# RTL-SDR.net
KiCad netlist of a schematic drawn in Altium Designer
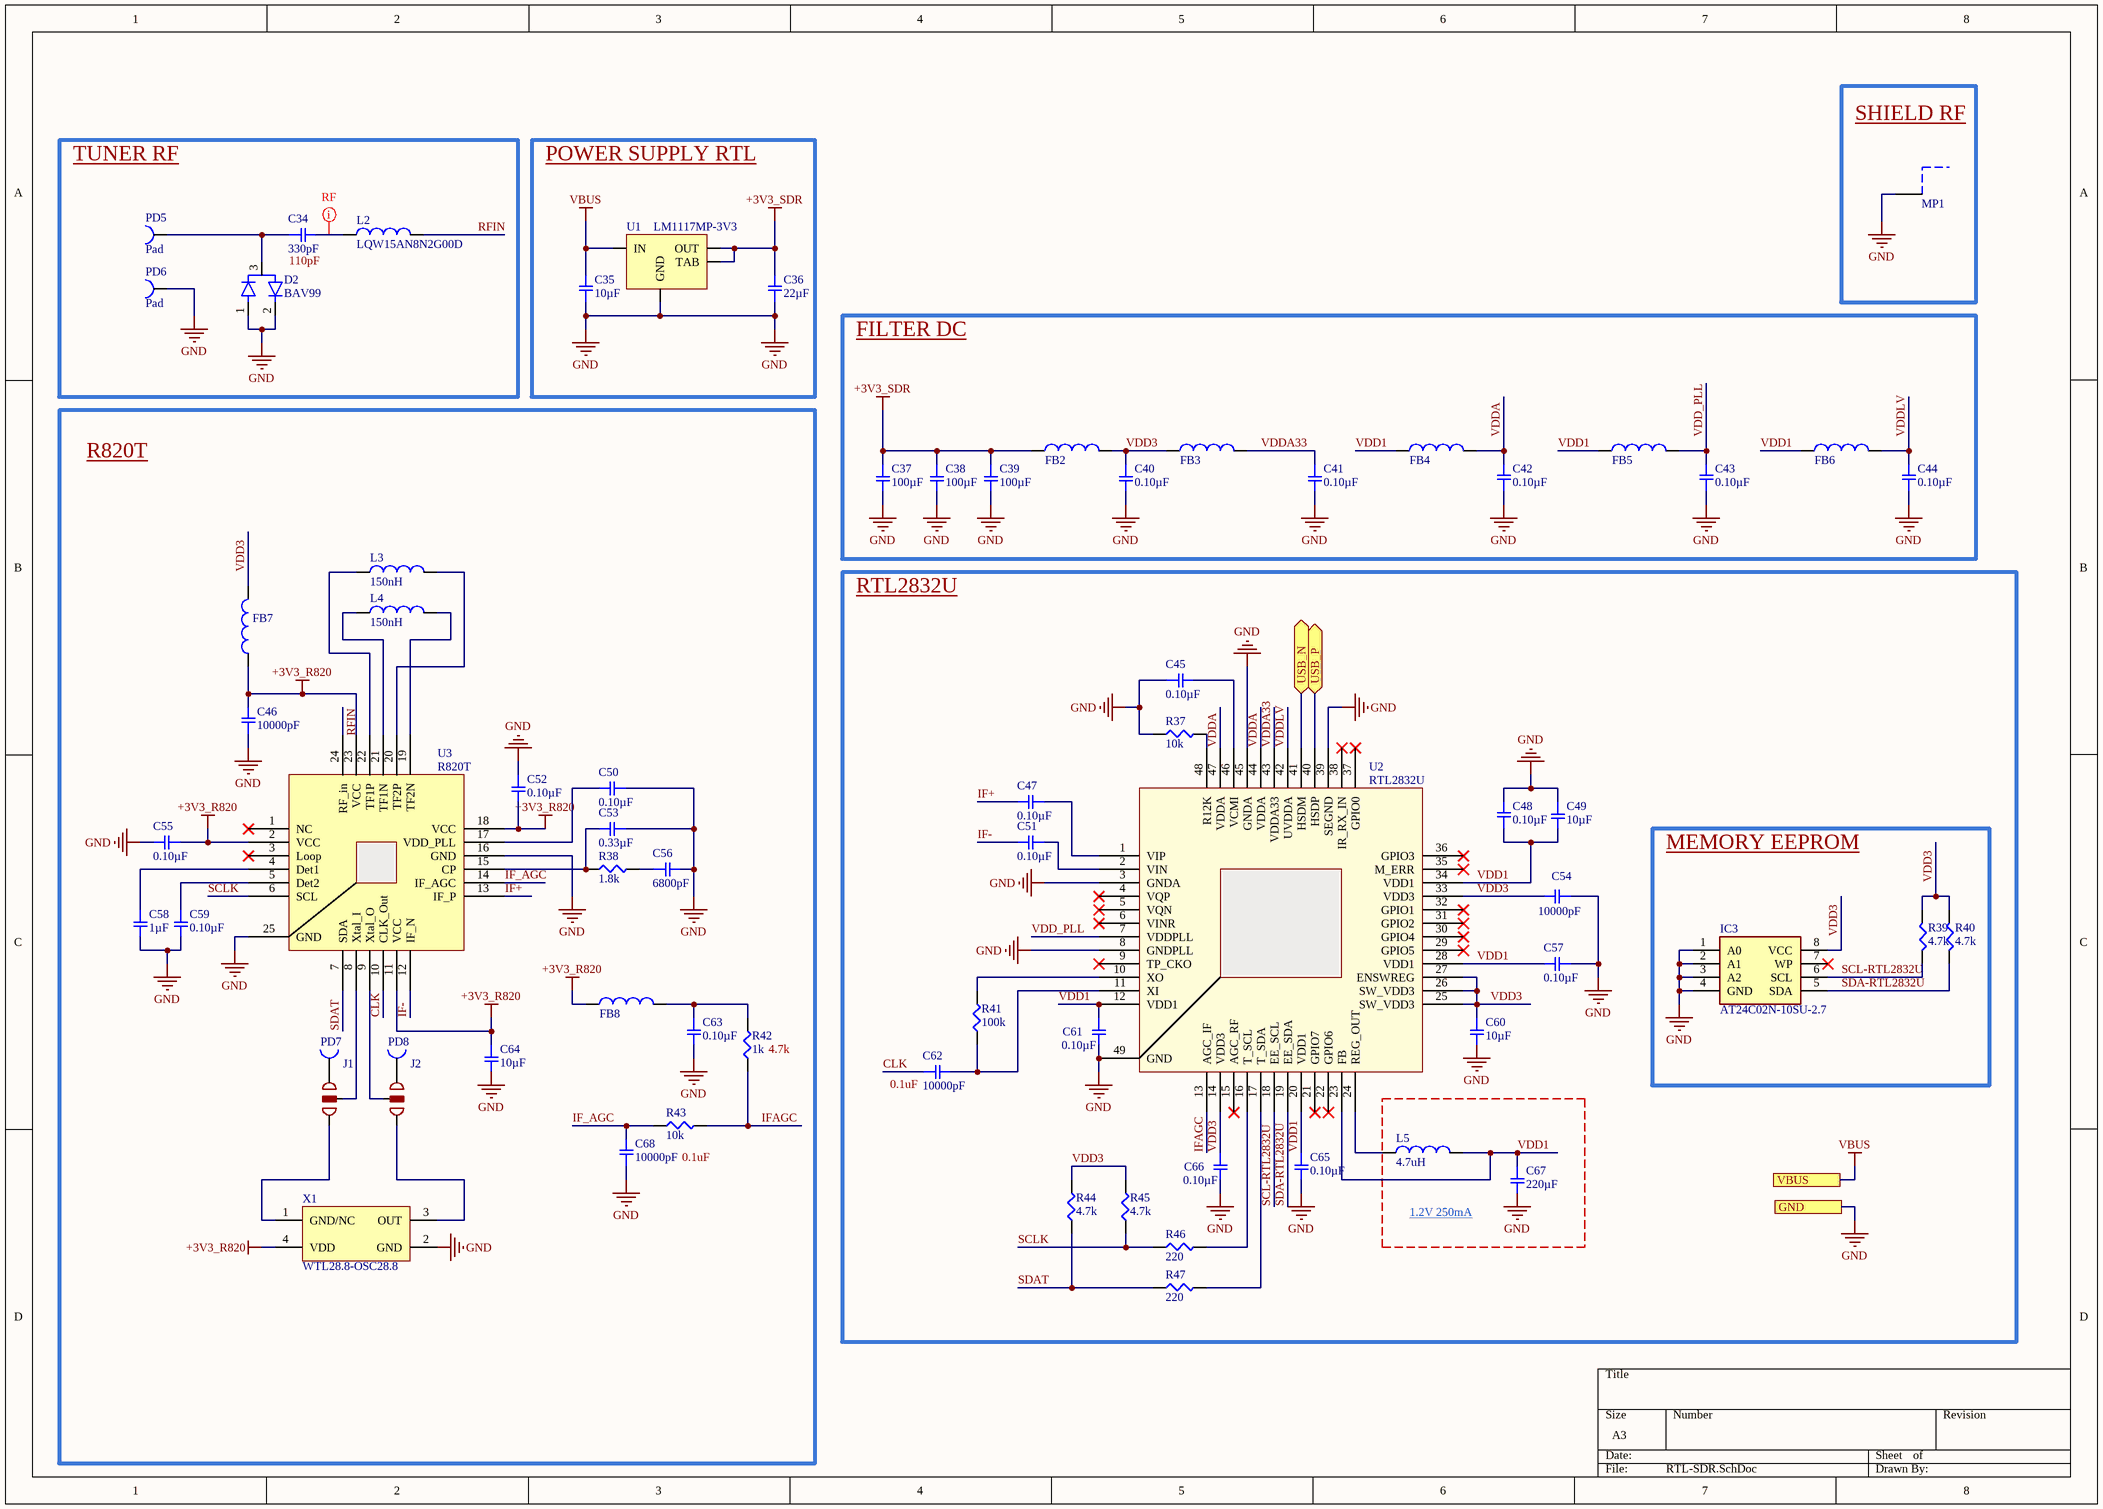
[diagram p0: RTL-SDR.SchDoc]

(export (version "E")
  (design (tool "Eeschema 10.0.6"))
  (components
    (comp (ref "C34")
      (value "330pF")
      (footprint "SMD-0402C")
      (description "CAP CER 330PF 25V NP0 0402")
      (fields
        (field (name "PART NUMBER") "GRM1555C1E331JA01D")
        (field (name "DIGI-KEY PART NUMBER") "490-8176-1-ND")
      )
      (libsource (lib "cap_murata") (part "CAPACITOR"))
    )
    (comp (ref "C35")
      (value "10µF")
      (footprint "SMD-0805C")
      (description "CAP CER 10UF 16V X6S 0805")
      (fields
        (field (name "PART NUMBER") "GRT21BC81C106KE01L")
        (field (name "DIGI-KEY PART NUMBER") "490-12343-1-ND")
      )
      (libsource (lib "cap_murata") (part "CAPACITOR"))
    )
    (comp (ref "C36")
      (value "22µF")
      (footprint "SMD-0805C")
      (description "CAP CER 22UF 16V X5R 0805")
      (fields
        (field (name "PART NUMBER") "GRT21BR61C226ME13L")
        (field (name "DIGI-KEY PART NUMBER") "490-12383-1-ND")
      )
      (libsource (lib "cap_murata") (part "CAPACITOR"))
    )
    (comp (ref "C37")
      (value "100µF")
      (footprint "SMD-1210C")
      (description "CAP CER 100UF 6.3V X7S 1210")
      (fields
        (field (name "PART NUMBER") "GRM32EC70J107ME15L")
        (field (name "DIGI-KEY PART NUMBER") "490-10530-1-ND")
      )
      (libsource (lib "cap_murata") (part "CAPACITOR"))
    )
    (comp (ref "C38")
      (value "100µF")
      (footprint "SMD-1210C")
      (description "CAP CER 100UF 6.3V X7S 1210")
      (fields
        (field (name "PART NUMBER") "GRM32EC70J107ME15L")
        (field (name "DIGI-KEY PART NUMBER") "490-10530-1-ND")
      )
      (libsource (lib "cap_murata") (part "CAPACITOR"))
    )
    (comp (ref "C39")
      (value "100µF")
      (footprint "SMD-1210C")
      (description "CAP CER 100UF 6.3V X7S 1210")
      (fields
        (field (name "PART NUMBER") "GRM32EC70J107ME15L")
        (field (name "DIGI-KEY PART NUMBER") "490-10530-1-ND")
      )
      (libsource (lib "cap_murata") (part "CAPACITOR"))
    )
    (comp (ref "C40")
      (value "0.10µF")
      (footprint "SMD-0402C")
      (description "CAP CER 0.1UF 16V X7R 0402")
      (fields
        (field (name "PART NUMBER") "GCM155R71C104KA55J")
        (field (name "DIGI-KEY PART NUMBER") "490-7998-1-ND")
      )
      (libsource (lib "cap_murata") (part "CAPACITOR"))
    )
    (comp (ref "C41")
      (value "0.10µF")
      (footprint "SMD-0402C")
      (description "CAP CER 0.1UF 16V X7R 0402")
      (fields
        (field (name "PART NUMBER") "GCM155R71C104KA55J")
        (field (name "DIGI-KEY PART NUMBER") "490-7998-1-ND")
      )
      (libsource (lib "cap_murata") (part "CAPACITOR"))
    )
    (comp (ref "C42")
      (value "0.10µF")
      (footprint "SMD-0402C")
      (description "CAP CER 0.1UF 16V X7R 0402")
      (fields
        (field (name "PART NUMBER") "GCM155R71C104KA55J")
        (field (name "DIGI-KEY PART NUMBER") "490-7998-1-ND")
      )
      (libsource (lib "cap_murata") (part "CAPACITOR"))
    )
    (comp (ref "C43")
      (value "0.10µF")
      (footprint "SMD-0402C")
      (description "CAP CER 0.1UF 16V X7R 0402")
      (fields
        (field (name "PART NUMBER") "GCM155R71C104KA55J")
        (field (name "DIGI-KEY PART NUMBER") "490-7998-1-ND")
      )
      (libsource (lib "cap_murata") (part "CAPACITOR"))
    )
    (comp (ref "C44")
      (value "0.10µF")
      (footprint "SMD-0402C")
      (description "CAP CER 0.1UF 16V X7R 0402")
      (fields
        (field (name "PART NUMBER") "GCM155R71C104KA55J")
        (field (name "DIGI-KEY PART NUMBER") "490-7998-1-ND")
      )
      (libsource (lib "cap_murata") (part "CAPACITOR"))
    )
    (comp (ref "C45")
      (value "0.10µF")
      (footprint "SMD-0402C")
      (description "CAP CER 0.1UF 16V X7R 0402")
      (fields
        (field (name "PART NUMBER") "GCM155R71C104KA55J")
        (field (name "DIGI-KEY PART NUMBER") "490-7998-1-ND")
      )
      (libsource (lib "cap_murata") (part "CAPACITOR"))
    )
    (comp (ref "C46")
      (value "10000pF")
      (footprint "SMD-0402C")
      (description "CAP CER 10000PF 16V X7R 0402")
      (fields
        (field (name "PART NUMBER") "GRM155R71C103KA01J")
        (field (name "DIGI-KEY PART NUMBER") "490-6326-1-ND")
      )
      (libsource (lib "cap_murata") (part "CAPACITOR"))
    )
    (comp (ref "C47")
      (value "0.10µF")
      (footprint "SMD-0402C")
      (description "CAP CER 0.1UF 16V X7R 0402")
      (fields
        (field (name "PART NUMBER") "GCM155R71C104KA55J")
        (field (name "DIGI-KEY PART NUMBER") "490-7998-1-ND")
      )
      (libsource (lib "cap_murata") (part "CAPACITOR"))
    )
    (comp (ref "C48")
      (value "0.10µF")
      (footprint "SMD-0402C")
      (description "CAP CER 0.1UF 16V X7R 0402")
      (fields
        (field (name "PART NUMBER") "GCM155R71C104KA55J")
        (field (name "DIGI-KEY PART NUMBER") "490-7998-1-ND")
      )
      (libsource (lib "cap_murata") (part "CAPACITOR"))
    )
    (comp (ref "C49")
      (value "10µF")
      (footprint "SMD-0603C")
      (description "CAP CER 10UF 16V X6S 0603")
      (fields
        (field (name "PART NUMBER") "GRT188C81C106ME13D")
        (field (name "DIGI-KEY PART NUMBER") "490-12286-1-ND")
      )
      (libsource (lib "cap_murata") (part "CAPACITOR"))
    )
    (comp (ref "C50")
      (value "0.10µF")
      (footprint "SMD-0402C")
      (description "CAP CER 0.1UF 16V X7R 0402")
      (fields
        (field (name "PART NUMBER") "GCM155R71C104KA55J")
        (field (name "DIGI-KEY PART NUMBER") "490-7998-1-ND")
      )
      (libsource (lib "cap_murata") (part "CAPACITOR"))
    )
    (comp (ref "C51")
      (value "0.10µF")
      (footprint "SMD-0402C")
      (description "CAP CER 0.1UF 16V X7R 0402")
      (fields
        (field (name "PART NUMBER") "GCM155R71C104KA55J")
        (field (name "DIGI-KEY PART NUMBER") "490-7998-1-ND")
      )
      (libsource (lib "cap_murata") (part "CAPACITOR"))
    )
    (comp (ref "C52")
      (value "0.10µF")
      (footprint "SMD-0402C")
      (description "CAP CER 0.1UF 16V X7R 0402")
      (fields
        (field (name "PART NUMBER") "GCM155R71C104KA55J")
        (field (name "DIGI-KEY PART NUMBER") "490-7998-1-ND")
      )
      (libsource (lib "cap_murata") (part "CAPACITOR"))
    )
    (comp (ref "C53")
      (value "0.33µF")
      (footprint "SMD-0402C")
      (description "CAP CER 0.33UF 10V X5R 0402")
      (fields
        (field (name "PART NUMBER") "GRM155R61A334KE15D")
        (field (name "DIGI-KEY PART NUMBER") "490-3263-1-ND")
      )
      (libsource (lib "cap_murata") (part "CAPACITOR"))
    )
    (comp (ref "C54")
      (value "10000pF")
      (footprint "SMD-0402C")
      (description "CAP CER 10000PF 16V X7R 0402")
      (fields
        (field (name "PART NUMBER") "GRM155R71C103KA01J")
        (field (name "DIGI-KEY PART NUMBER") "490-6326-1-ND")
      )
      (libsource (lib "cap_murata") (part "CAPACITOR"))
    )
    (comp (ref "C55")
      (value "0.10µF")
      (footprint "SMD-0402C")
      (description "CAP CER 0.1UF 16V X7R 0402")
      (fields
        (field (name "PART NUMBER") "GCM155R71C104KA55J")
        (field (name "DIGI-KEY PART NUMBER") "490-7998-1-ND")
      )
      (libsource (lib "cap_murata") (part "CAPACITOR"))
    )
    (comp (ref "C56")
      (value "6800pF")
      (footprint "SMD-0402C")
      (description "CAP CER 6800PF 25V X7R 0402")
      (fields
        (field (name "PART NUMBER") "GRM155R71E682KA01D")
        (field (name "DIGI-KEY PART NUMBER") "490-1310-1-ND")
      )
      (libsource (lib "cap_murata") (part "CAPACITOR"))
    )
    (comp (ref "C57")
      (value "0.10µF")
      (footprint "SMD-0402C")
      (description "CAP CER 0.1UF 16V X7R 0402")
      (fields
        (field (name "PART NUMBER") "GCM155R71C104KA55J")
        (field (name "DIGI-KEY PART NUMBER") "490-7998-1-ND")
      )
      (libsource (lib "cap_murata") (part "CAPACITOR"))
    )
    (comp (ref "C58")
      (value "1µF")
      (footprint "SMD-0402C")
      (description "CAP CER 1UF 25V X5R 0402")
      (fields
        (field (name "PART NUMBER") "GRM155R61E105MA12D")
        (field (name "DIGI-KEY PART NUMBER") "490-10018-1-ND")
      )
      (libsource (lib "cap_murata") (part "CAPACITOR"))
    )
    (comp (ref "C59")
      (value "0.10µF")
      (footprint "SMD-0402C")
      (description "CAP CER 0.1UF 16V X7R 0402")
      (fields
        (field (name "PART NUMBER") "GCM155R71C104KA55J")
        (field (name "DIGI-KEY PART NUMBER") "490-7998-1-ND")
      )
      (libsource (lib "cap_murata") (part "CAPACITOR"))
    )
    (comp (ref "C60")
      (value "10µF")
      (footprint "SMD-0603C")
      (description "CAP CER 10UF 16V X6S 0603")
      (fields
        (field (name "PART NUMBER") "GRT188C81C106ME13D")
        (field (name "DIGI-KEY PART NUMBER") "490-12286-1-ND")
      )
      (libsource (lib "cap_murata") (part "CAPACITOR"))
    )
    (comp (ref "C61")
      (value "0.10µF")
      (footprint "SMD-0402C")
      (description "CAP CER 0.1UF 16V X7R 0402")
      (fields
        (field (name "PART NUMBER") "GCM155R71C104KA55J")
        (field (name "DIGI-KEY PART NUMBER") "490-7998-1-ND")
      )
      (libsource (lib "cap_murata") (part "CAPACITOR"))
    )
    (comp (ref "C62")
      (value "10000pF")
      (footprint "SMD-0402C")
      (description "CAP CER 10000PF 16V X7R 0402")
      (fields
        (field (name "PART NUMBER") "GRM155R71C103KA01D")
        (field (name "DIGI-KEY PART NUMBER") "490-1313-1-ND")
      )
      (libsource (lib "cap_murata") (part "CAPACITOR"))
    )
    (comp (ref "C63")
      (value "0.10µF")
      (footprint "SMD-0402C")
      (description "CAP CER 0.1UF 16V X7R 0402")
      (fields
        (field (name "PART NUMBER") "GCM155R71C104KA55J")
        (field (name "DIGI-KEY PART NUMBER") "490-7998-1-ND")
      )
      (libsource (lib "cap_murata") (part "CAPACITOR"))
    )
    (comp (ref "C64")
      (value "10µF")
      (footprint "SMD-0805C")
      (description "CAP CER 10UF 16V X6S 0805")
      (fields
        (field (name "PART NUMBER") "GRT21BC81C106KE01L")
        (field (name "DIGI-KEY PART NUMBER") "490-12343-1-ND")
      )
      (libsource (lib "cap_murata") (part "CAPACITOR"))
    )
    (comp (ref "C65")
      (value "0.10µF")
      (footprint "SMD-0402C")
      (description "CAP CER 0.1UF 16V X7R 0402")
      (fields
        (field (name "PART NUMBER") "GCM155R71C104KA55J")
        (field (name "DIGI-KEY PART NUMBER") "490-7998-1-ND")
      )
      (libsource (lib "cap_murata") (part "CAPACITOR"))
    )
    (comp (ref "C66")
      (value "0.10µF")
      (footprint "SMD-0402C")
      (description "CAP CER 0.1UF 16V X7R 0402")
      (fields
        (field (name "PART NUMBER") "GCM155R71C104KA55J")
        (field (name "DIGI-KEY PART NUMBER") "490-7998-1-ND")
      )
      (libsource (lib "cap_murata") (part "CAPACITOR"))
    )
    (comp (ref "C67")
      (value "220µF")
      (footprint "SMD-1210C")
      (description "CAP CER 220UF 4V X6S 1210")
      (fields
        (field (name "PART NUMBER") "GRM32EC80G227ME05L")
        (field (name "DIGI-KEY PART NUMBER") "490-13973-1-ND")
      )
      (libsource (lib "cap_murata") (part "CAPACITOR"))
    )
    (comp (ref "C68")
      (value "10000pF")
      (footprint "SMD-0402C")
      (description "CAP CER 10000PF 16V X7R 0402")
      (fields
        (field (name "PART NUMBER") "GRM155R71C103KA01J")
        (field (name "DIGI-KEY PART NUMBER") "490-6326-1-ND")
      )
      (libsource (lib "cap_murata") (part "CAPACITOR"))
    )
    (comp (ref "D2")
      (value "BAV99")
      (footprint "DIO_BAV99")
      (fields (field (name "MF") "ON Semiconductor"))
      (libsource (lib "DSD_Aerobits_RPI4_OLED") (part "BAV99"))
    )
    (comp (ref "FB2")
      (value "10Ohm")
      (footprint "WE-CBA_0402_L1W0.5H0.5_HC")
      (description "WE-CBA SMT EMI Suppression Ferrite Bead, size 0402, 10Ohm, 1.5A")
      (fields
        (field (name "MANUFACTURER PART NUMBER") "782423100")
        (field (name "MANUFACTURER") "Wurth Elektronik")
      )
      (libsource (lib "Altium_WE-CBA (rev22d)") (part "782423100"))
    )
    (comp (ref "FB3")
      (value "10Ohm")
      (footprint "WE-CBA_0402_L1W0.5H0.5_HC")
      (description "WE-CBA SMT EMI Suppression Ferrite Bead, size 0402, 10Ohm, 1.5A")
      (fields
        (field (name "MANUFACTURER PART NUMBER") "782423100")
        (field (name "MANUFACTURER") "Wurth Elektronik")
      )
      (libsource (lib "Altium_WE-CBA (rev22d)") (part "782423100"))
    )
    (comp (ref "FB4")
      (value "10Ohm")
      (footprint "WE-CBA_0402_L1W0.5H0.5_HC")
      (description "WE-CBA SMT EMI Suppression Ferrite Bead, size 0402, 10Ohm, 1.5A")
      (fields
        (field (name "MANUFACTURER PART NUMBER") "782423100")
        (field (name "MANUFACTURER") "Wurth Elektronik")
      )
      (libsource (lib "Altium_WE-CBA (rev22d)") (part "782423100"))
    )
    (comp (ref "FB5")
      (value "10Ohm")
      (footprint "WE-CBA_0402_L1W0.5H0.5_HC")
      (description "WE-CBA SMT EMI Suppression Ferrite Bead, size 0402, 10Ohm, 1.5A")
      (fields
        (field (name "MANUFACTURER PART NUMBER") "782423100")
        (field (name "MANUFACTURER") "Wurth Elektronik")
      )
      (libsource (lib "Altium_WE-CBA (rev22d)") (part "782423100"))
    )
    (comp (ref "FB6")
      (value "10Ohm")
      (footprint "WE-CBA_0402_L1W0.5H0.5_HC")
      (description "WE-CBA SMT EMI Suppression Ferrite Bead, size 0402, 10Ohm, 1.5A")
      (fields
        (field (name "MANUFACTURER PART NUMBER") "782423100")
        (field (name "MANUFACTURER") "Wurth Elektronik")
      )
      (libsource (lib "Altium_WE-CBA (rev22d)") (part "782423100"))
    )
    (comp (ref "FB7")
      (value "10Ohm")
      (footprint "WE-CBA_0402_L1W0.5H0.5_HC")
      (description "WE-CBA SMT EMI Suppression Ferrite Bead, size 0402, 10Ohm, 1.5A")
      (fields
        (field (name "MANUFACTURER PART NUMBER") "782423100")
        (field (name "MANUFACTURER") "Wurth Elektronik")
      )
      (libsource (lib "Altium_WE-CBA (rev22d)") (part "782423100"))
    )
    (comp (ref "FB8")
      (value "10Ohm")
      (footprint "WE-CBA_0402_L1W0.5H0.5_HC")
      (description "WE-CBA SMT EMI Suppression Ferrite Bead, size 0402, 10Ohm, 1.5A")
      (fields
        (field (name "MANUFACTURER PART NUMBER") "782423100")
        (field (name "MANUFACTURER") "Wurth Elektronik")
      )
      (libsource (lib "Altium_WE-CBA (rev22d)") (part "782423100"))
    )
    (comp (ref "IC3")
      (value "AT24C02N-10SU-2.7")
      (footprint "SamacSys:SOIC127P600X175-8N")
      (description "Integrated Circuit")
      (libsource (lib "SamacSys") (part "AT24C02N-10SU-2.7"))
    )
    (comp (ref "J1") (value "jumper") (footprint "jumperTreestate") (libsource (lib "") (part "jumper_1")))
    (comp (ref "J2")
      (value "jumper")
      (footprint "jumperTreestate")
      (libsource (lib "Jumpers") (part "jumper"))
    )
    (comp (ref "L2")
      (value "LQW15AN8N2G00D")
      (footprint "INDC1006X60N")
      (description "LQW15A 0,0082ÂµH 540mA 2% WWT")
      (libsource (lib "DSD_Aerobits_RPI4_OLED") (part "LQW15AN8N2G00D"))
    )
    (comp (ref "L3")
      (value "150nH")
      (footprint "INDC1608X100N")
      (description "CHIP COIL LQW18A")
      (fields (field (name "MP") "LQW18ANR15J00D"))
      (libsource (lib "DSD_Aerobits_RPI4_OLED") (part "LQW18ANR15J00D"))
    )
    (comp (ref "L4")
      (value "150nH")
      (footprint "INDC1608X100N")
      (description "CHIP COIL LQW18A")
      (fields (field (name "MP") "LQW18ANR15J00D"))
      (libsource (lib "DSD_Aerobits_RPI4_OLED") (part "LQW18ANR15J00D"))
    )
    (comp (ref "L5")
      (value "4.7uH")
      (footprint "INDC2518X200N")
      (description "Ind Power Chip Wirewound 4.7uH 20% 7.96MHz Ferrite 1.1A 1007 T/R")
      (fields (field (name "MP") "CB2518T4R7M"))
      (libsource (lib "DSD_Aerobits_RPI4_OLED") (part "CB2518T4R7M"))
    )
    (comp (ref "MP1")
      (value "36903205S")
      (footprint "36903205S")
      (description "WE-SHC Shielding Cabinet, One Piece, Tin Plated, Tape and Reel, 20x20x3mm")
      (fields (field (name "MANUFACTURER") "Wurth Elektronik"))
      (libsource (lib "WE-SHC (rev22a) (1)") (part "36903205S"))
    )
    (comp (ref "PD5") (value "Pad") (footprint "pad") (libsource (lib "Castellated_Pad") (part "Pad")))
    (comp (ref "PD6") (value "Pad") (footprint "pad") (libsource (lib "Castellated_Pad") (part "Pad")))
    (comp (ref "PD7") (value "Pad") (footprint "pad") (libsource (lib "Castellated_Pad") (part "Pad")))
    (comp (ref "PD8") (value "Pad") (footprint "pad") (libsource (lib "Castellated_Pad") (part "Pad")))
    (comp (ref "R37")
      (value "10k")
      (footprint "SMD-0402-RES")
      (description "RES SMD 10K OHM 1% 1/10W 0402")
      (fields
        (field (name "PART NUMBER") "ERJ-2RKF1002X")
        (field (name "DIGI-KEY PART NUMBER") "P10.0KLCT-ND")
      )
      (libsource (lib "res_panasonic_erj_xls") (part "RESISTOR"))
    )
    (comp (ref "R38")
      (value "1.8k")
      (footprint "SMD-0402-RES")
      (description "RES SMD 1.8K OHM 5% 1/10W 0402")
      (fields (field (name "PART NUMBER") "ERJ-2GEJ182X") (field (name "DIGI-KEY PART NUMBER") "P1.8KJCT-ND"))
      (libsource (lib "res_panasonic_erj_xls") (part "RESISTOR"))
    )
    (comp (ref "R39")
      (value "4.7k")
      (footprint "SMD-0402-RES")
      (description "RES SMD 4.7K OHM 1% 1/10W 0402")
      (fields
        (field (name "PART NUMBER") "ERJ-2RKF4701X")
        (field (name "DIGI-KEY PART NUMBER") "P4.70KLCT-ND")
      )
      (libsource (lib "res_panasonic_erj_xls") (part "RESISTOR"))
    )
    (comp (ref "R40")
      (value "4.7k")
      (footprint "SMD-0402-RES")
      (description "RES SMD 4.7K OHM 1% 1/10W 0402")
      (fields
        (field (name "PART NUMBER") "ERJ-2RKF4701X")
        (field (name "DIGI-KEY PART NUMBER") "P4.70KLCT-ND")
      )
      (libsource (lib "res_panasonic_erj_xls") (part "RESISTOR"))
    )
    (comp (ref "R41")
      (value "100k")
      (footprint "SMD-0402-RES")
      (description "RES SMD 100K OHM 1% 1/10W 0402")
      (fields
        (field (name "PART NUMBER") "ERJ-2RKF1003X")
        (field (name "DIGI-KEY PART NUMBER") "P100KLCT-ND")
      )
      (libsource (lib "res_panasonic_erj_xls") (part "RESISTOR"))
    )
    (comp (ref "R42")
      (value "1k")
      (footprint "SMD-0402-RES")
      (description "RES SMD 1K OHM 5% 1/10W 0402")
      (fields (field (name "PART NUMBER") "ERJ-2GEJ102X") (field (name "DIGI-KEY PART NUMBER") "P1.0KJCT-ND"))
      (libsource (lib "res_panasonic_erj_xls") (part "RESISTOR"))
    )
    (comp (ref "R43")
      (value "10k")
      (footprint "SMD-0402-RES")
      (description "RES SMD 10K OHM 1% 1/10W 0402")
      (fields
        (field (name "PART NUMBER") "ERJ-2RKF1002X")
        (field (name "DIGI-KEY PART NUMBER") "P10.0KLCT-ND")
      )
      (libsource (lib "res_panasonic_erj_xls") (part "RESISTOR"))
    )
    (comp (ref "R44")
      (value "4.7k")
      (footprint "SMD-0402-RES")
      (description "RES SMD 4.7K OHM 1% 1/10W 0402")
      (fields
        (field (name "PART NUMBER") "ERJ-2RKF4701X")
        (field (name "DIGI-KEY PART NUMBER") "P4.70KLCT-ND")
      )
      (libsource (lib "res_panasonic_erj_xls") (part "RESISTOR"))
    )
    (comp (ref "R45")
      (value "4.7k")
      (footprint "SMD-0402-RES")
      (description "RES SMD 4.7K OHM 1% 1/10W 0402")
      (fields
        (field (name "PART NUMBER") "ERJ-2RKF4701X")
        (field (name "DIGI-KEY PART NUMBER") "P4.70KLCT-ND")
      )
      (libsource (lib "res_panasonic_erj_xls") (part "RESISTOR"))
    )
    (comp (ref "R46")
      (value "220")
      (footprint "SMD-0402-RES")
      (description "RES SMD 220 OHM 5% 1/5W 0402")
      (fields (field (name "PART NUMBER") "ERJ-PA2J221X") (field (name "DIGI-KEY PART NUMBER") "P17189CT-ND"))
      (libsource (lib "res_panasonic_erj_xls") (part "RESISTOR"))
    )
    (comp (ref "R47")
      (value "220")
      (footprint "SMD-0402-RES")
      (description "RES SMD 220 OHM 5% 1/5W 0402")
      (fields (field (name "PART NUMBER") "ERJ-PA2J221X") (field (name "DIGI-KEY PART NUMBER") "P17189CT-ND"))
      (libsource (lib "res_panasonic_erj_xls") (part "RESISTOR"))
    )
    (comp (ref "U1")
      (value "LM1117MP-3V3")
      (footprint "SOT223")
      (description "800mA Low-Dropout Linear Regulator")
      (fields
        (field (name "PARTNUMBER") "LM1117MP-3.3")
        (field (name "MANUFACTURER") "National Semiconductor")
        (field (name "PUBLISHER") "Altium Limited")
      )
      (libsource (lib "biblioteka_schematic") (part "LM1117MP-3V3"))
    )
    (comp (ref "U2")
      (value "RTL2832U")
      (footprint "QFN40P600X600X84_HS-49N")
      (description "RTL2832U DVB-T COFDM Demodulator + USB 2.0")
      (fields (field (name "MANUFACTURER") "Realtek") (field (name "PUBLISHER") "ftg"))
      (libsource (lib "DSD_Aerobits_RPI4_OLED") (part "RTL2832U"))
    )
    (comp (ref "U3")
      (value "R820T")
      (footprint "QFN50P400X400X85_HS-25N_r820t")
      (libsource (lib "DSD_Aerobits_RPI4_OLED") (part "R820T"))
    )
    (comp (ref "X1")
      (value "WTL28.8-OSC28.8")
      (footprint "WTL28.8-OSC28.8")
      (libsource (lib "DSD_Aerobits_RPI4_OLED") (part "WTL28.8-OSC28.8"))
    )
  )
  (nets
    (net (code "1") (name "+3V3_R820") (class "Default")
      (node (ref "C46") (pin "2") (pinfunction "2_2") (pintype "passive"))
      (node (ref "C52") (pin "2") (pinfunction "2_2") (pintype "passive"))
      (node (ref "C55") (pin "1") (pinfunction "1_1") (pintype "passive"))
      (node (ref "C64") (pin "1") (pinfunction "1_1") (pintype "passive"))
      (node (ref "FB7") (pin "1") (pinfunction "1_1") (pintype "passive"))
      (node (ref "FB8") (pin "1") (pinfunction "1_1") (pintype "passive"))
      (node (ref "U3") (pin "11") (pinfunction "VCC_11") (pintype "passive"))
      (node (ref "U3") (pin "18") (pinfunction "VCC_18") (pintype "passive"))
      (node (ref "U3") (pin "2") (pinfunction "VCC_2") (pintype "passive"))
      (node (ref "U3") (pin "23") (pinfunction "VCC_23") (pintype "passive"))
      (node (ref "X1") (pin "4") (pinfunction "VDD_4") (pintype "passive"))
    )
    (net (code "2") (name "+3V3_SDR") (class "Default")
      (node (ref "C36") (pin "2") (pinfunction "2_2") (pintype "passive"))
      (node (ref "C37") (pin "1") (pinfunction "1_1") (pintype "passive"))
      (node (ref "C38") (pin "1") (pinfunction "1_1") (pintype "passive"))
      (node (ref "C39") (pin "1") (pinfunction "1_1") (pintype "passive"))
      (node (ref "FB2") (pin "1") (pinfunction "1_1") (pintype "passive"))
      (node (ref "U1") (pin "2") (pinfunction "OUT_2") (pintype "power_in"))
      (node (ref "U1") (pin "4") (pinfunction "TAB_4") (pintype "power_in"))
    )
    (net (code "3") (name "/CLK") (class "Default")
      (node (ref "C62") (pin "1") (pinfunction "1_1") (pintype "passive"))
      (node (ref "U3") (pin "10") (pinfunction "CLK_Out_10") (pintype "passive"))
    )
    (net (code "4") (name "/IF+") (class "Default")
      (node (ref "C47") (pin "2") (pinfunction "2_2") (pintype "passive"))
      (node (ref "U3") (pin "13") (pinfunction "IF_P_13") (pintype "passive"))
    )
    (net (code "5") (name "/IF-") (class "Default")
      (node (ref "C51") (pin "2") (pinfunction "2_2") (pintype "passive"))
      (node (ref "U3") (pin "12") (pinfunction "IF_N_12") (pintype "passive"))
    )
    (net (code "6") (name "/IFAGC") (class "Default")
      (node (ref "R42") (pin "1") (pinfunction "1_1") (pintype "passive"))
      (node (ref "R43") (pin "2") (pinfunction "2_2") (pintype "passive"))
      (node (ref "U2") (pin "13") (pinfunction "AGC_IF_13") (pintype "passive"))
    )
    (net (code "7") (name "/IF_AGC") (class "Default")
      (node (ref "C68") (pin "2") (pinfunction "2_2") (pintype "passive"))
      (node (ref "R43") (pin "1") (pinfunction "1_1") (pintype "passive"))
      (node (ref "U3") (pin "14") (pinfunction "IF_AGC_14") (pintype "passive"))
    )
    (net (code "8") (name "/RFIN") (class "Default")
      (node (ref "L2") (pin "2") (pinfunction "2_2") (pintype "passive"))
      (node (ref "U3") (pin "24") (pinfunction "RF_in_24") (pintype "passive"))
    )
    (net (code "9") (name "/SCL-RTL2832U") (class "Default")
      (node (ref "IC3") (pin "6") (pinfunction "SCL_6") (pintype "passive"))
      (node (ref "R39") (pin "1") (pinfunction "1_1") (pintype "passive"))
      (node (ref "U2") (pin "18") (pinfunction "EE_SCL_18") (pintype "passive"))
    )
    (net (code "10") (name "/SCLK") (class "Default")
      (node (ref "R45") (pin "1") (pinfunction "1_1") (pintype "passive"))
      (node (ref "R46") (pin "1") (pinfunction "1_1") (pintype "passive"))
      (node (ref "U3") (pin "6") (pinfunction "SCL_6") (pintype "passive"))
    )
    (net (code "11") (name "/SDA-RTL2832U") (class "Default")
      (node (ref "IC3") (pin "5") (pinfunction "SDA_5") (pintype "passive"))
      (node (ref "R40") (pin "1") (pinfunction "1_1") (pintype "passive"))
      (node (ref "U2") (pin "19") (pinfunction "EE_SDA_19") (pintype "passive"))
    )
    (net (code "12") (name "/SDAT") (class "Default")
      (node (ref "R44") (pin "1") (pinfunction "1_1") (pintype "passive"))
      (node (ref "R47") (pin "1") (pinfunction "1_1") (pintype "passive"))
      (node (ref "U3") (pin "7") (pinfunction "SDA_7") (pintype "passive"))
    )
    (net (code "13") (name "/USB_N") (class "Default")
      (node (ref "U2") (pin "41") (pinfunction "HSDM_41") (pintype "passive"))
    )
    (net (code "14") (name "/USB_P") (class "Default")
      (node (ref "U2") (pin "40") (pinfunction "HSDP_40") (pintype "passive"))
    )
    (net (code "15") (name "/VDD1") (class "Default")
      (node (ref "C48") (pin "1") (pinfunction "1_1") (pintype "passive"))
      (node (ref "C49") (pin "2") (pinfunction "2_2") (pintype "passive"))
      (node (ref "C57") (pin "2") (pinfunction "2_2") (pintype "passive"))
      (node (ref "C61") (pin "1") (pinfunction "1_1") (pintype "passive"))
      (node (ref "C65") (pin "1") (pinfunction "1_1") (pintype "passive"))
      (node (ref "C67") (pin "1") (pinfunction "1_1") (pintype "passive"))
      (node (ref "FB4") (pin "1") (pinfunction "1_1") (pintype "passive"))
      (node (ref "FB5") (pin "1") (pinfunction "1_1") (pintype "passive"))
      (node (ref "FB6") (pin "1") (pinfunction "1_1") (pintype "passive"))
      (node (ref "L5") (pin "2") (pinfunction "2_2") (pintype "passive"))
      (node (ref "U2") (pin "12") (pinfunction "VDD1_12") (pintype "passive"))
      (node (ref "U2") (pin "20") (pinfunction "VDD1_20") (pintype "passive"))
      (node (ref "U2") (pin "23") (pinfunction "FB_23") (pintype "passive"))
      (node (ref "U2") (pin "28") (pinfunction "VDD1_28") (pintype "passive"))
      (node (ref "U2") (pin "34") (pinfunction "VDD1_34") (pintype "passive"))
    )
    (net (code "16") (name "/VDD3") (class "Default")
      (node (ref "C40") (pin "1") (pinfunction "1_1") (pintype "passive"))
      (node (ref "C54") (pin "2") (pinfunction "2_2") (pintype "passive"))
      (node (ref "C60") (pin "1") (pinfunction "1_1") (pintype "passive"))
      (node (ref "C66") (pin "1") (pinfunction "1_1") (pintype "passive"))
      (node (ref "FB2") (pin "2") (pinfunction "2_2") (pintype "passive"))
      (node (ref "FB3") (pin "1") (pinfunction "1_1") (pintype "passive"))
      (node (ref "FB7") (pin "2") (pinfunction "2_2") (pintype "passive"))
      (node (ref "IC3") (pin "8") (pinfunction "VCC_8") (pintype "passive"))
      (node (ref "R39") (pin "2") (pinfunction "2_2") (pintype "passive"))
      (node (ref "R40") (pin "2") (pinfunction "2_2") (pintype "passive"))
      (node (ref "R44") (pin "2") (pinfunction "2_2") (pintype "passive"))
      (node (ref "R45") (pin "2") (pinfunction "2_2") (pintype "passive"))
      (node (ref "U2") (pin "14") (pinfunction "VDD3_14") (pintype "passive"))
      (node (ref "U2") (pin "25") (pinfunction "SW_VDD3_25") (pintype "passive"))
      (node (ref "U2") (pin "26") (pinfunction "SW_VDD3_26") (pintype "passive"))
      (node (ref "U2") (pin "27") (pinfunction "ENSWREG_27") (pintype "passive"))
      (node (ref "U2") (pin "33") (pinfunction "VDD3_33") (pintype "passive"))
    )
    (net (code "17") (name "/VDDA") (class "Default")
      (node (ref "C42") (pin "2") (pinfunction "2_2") (pintype "passive"))
      (node (ref "FB4") (pin "2") (pinfunction "2_2") (pintype "passive"))
      (node (ref "U2") (pin "44") (pinfunction "VDDA_44") (pintype "passive"))
      (node (ref "U2") (pin "47") (pinfunction "VDDA_47") (pintype "passive"))
    )
    (net (code "18") (name "/VDDA33") (class "Default")
      (node (ref "C41") (pin "1") (pinfunction "1_1") (pintype "passive"))
      (node (ref "FB3") (pin "2") (pinfunction "2_2") (pintype "passive"))
      (node (ref "U2") (pin "43") (pinfunction "VDDA33_43") (pintype "passive"))
    )
    (net (code "19") (name "/VDDLV") (class "Default")
      (node (ref "C44") (pin "2") (pinfunction "2_2") (pintype "passive"))
      (node (ref "FB6") (pin "2") (pinfunction "2_2") (pintype "passive"))
      (node (ref "U2") (pin "42") (pinfunction "UVDDA_42") (pintype "passive"))
    )
    (net (code "20") (name "/VDD_PLL") (class "Default")
      (node (ref "C43") (pin "2") (pinfunction "2_2") (pintype "passive"))
      (node (ref "FB5") (pin "2") (pinfunction "2_2") (pintype "passive"))
      (node (ref "U2") (pin "7") (pinfunction "VDDPLL_7") (pintype "passive"))
    )
    (net (code "21") (name "GND") (class "Default")
      (node (ref "C35") (pin "1") (pinfunction "1_1") (pintype "passive"))
      (node (ref "C36") (pin "1") (pinfunction "1_1") (pintype "passive"))
      (node (ref "C37") (pin "2") (pinfunction "2_2") (pintype "passive"))
      (node (ref "C38") (pin "2") (pinfunction "2_2") (pintype "passive"))
      (node (ref "C39") (pin "2") (pinfunction "2_2") (pintype "passive"))
      (node (ref "C40") (pin "2") (pinfunction "2_2") (pintype "passive"))
      (node (ref "C41") (pin "2") (pinfunction "2_2") (pintype "passive"))
      (node (ref "C42") (pin "1") (pinfunction "1_1") (pintype "passive"))
      (node (ref "C43") (pin "1") (pinfunction "1_1") (pintype "passive"))
      (node (ref "C44") (pin "1") (pinfunction "1_1") (pintype "passive"))
      (node (ref "C45") (pin "1") (pinfunction "1_1") (pintype "passive"))
      (node (ref "C46") (pin "1") (pinfunction "1_1") (pintype "passive"))
      (node (ref "C48") (pin "2") (pinfunction "2_2") (pintype "passive"))
      (node (ref "C49") (pin "1") (pinfunction "1_1") (pintype "passive"))
      (node (ref "C50") (pin "1") (pinfunction "1_1") (pintype "passive"))
      (node (ref "C52") (pin "1") (pinfunction "1_1") (pintype "passive"))
      (node (ref "C53") (pin "1") (pinfunction "1_1") (pintype "passive"))
      (node (ref "C54") (pin "1") (pinfunction "1_1") (pintype "passive"))
      (node (ref "C55") (pin "2") (pinfunction "2_2") (pintype "passive"))
      (node (ref "C56") (pin "2") (pinfunction "2_2") (pintype "passive"))
      (node (ref "C57") (pin "1") (pinfunction "1_1") (pintype "passive"))
      (node (ref "C58") (pin "2") (pinfunction "2_2") (pintype "passive"))
      (node (ref "C59") (pin "2") (pinfunction "2_2") (pintype "passive"))
      (node (ref "C60") (pin "2") (pinfunction "2_2") (pintype "passive"))
      (node (ref "C61") (pin "2") (pinfunction "2_2") (pintype "passive"))
      (node (ref "C63") (pin "2") (pinfunction "2_2") (pintype "passive"))
      (node (ref "C64") (pin "2") (pinfunction "2_2") (pintype "passive"))
      (node (ref "C65") (pin "2") (pinfunction "2_2") (pintype "passive"))
      (node (ref "C66") (pin "2") (pinfunction "2_2") (pintype "passive"))
      (node (ref "C67") (pin "2") (pinfunction "2_2") (pintype "passive"))
      (node (ref "C68") (pin "1") (pinfunction "1_1") (pintype "passive"))
      (node (ref "D2") (pin "1") (pinfunction "1_1") (pintype "passive"))
      (node (ref "D2") (pin "2") (pinfunction "2_2") (pintype "passive"))
      (node (ref "IC3") (pin "1") (pinfunction "A0_1") (pintype "passive"))
      (node (ref "IC3") (pin "2") (pinfunction "A1_2") (pintype "passive"))
      (node (ref "IC3") (pin "3") (pinfunction "A2_3") (pintype "passive"))
      (node (ref "IC3") (pin "4") (pinfunction "GND_4") (pintype "passive"))
      (node (ref "MP1") (pin "1") (pinfunction "1_1") (pintype "passive"))
      (node (ref "PD6") (pin "1") (pinfunction "0_1") (pintype "passive"))
      (node (ref "R37") (pin "1") (pinfunction "1_1") (pintype "passive"))
      (node (ref "U1") (pin "1") (pinfunction "GND_1") (pintype "power_in"))
      (node (ref "U2") (pin "3") (pinfunction "GNDA_3") (pintype "passive"))
      (node (ref "U2") (pin "39") (pinfunction "SEGND_39") (pintype "passive"))
      (node (ref "U2") (pin "45") (pinfunction "GNDA_45") (pintype "passive"))
      (node (ref "U2") (pin "49") (pinfunction "GND_49") (pintype "passive"))
      (node (ref "U2") (pin "8") (pinfunction "GNDPLL_8") (pintype "passive"))
      (node (ref "U3") (pin "16") (pinfunction "GND_16") (pintype "passive"))
      (node (ref "U3") (pin "25") (pinfunction "GND_25") (pintype "passive"))
      (node (ref "X1") (pin "2") (pinfunction "GND_2") (pintype "passive"))
    )
    (net (code "22") (name "Net-(C34-Pad2)") (class "Default")
      (node (ref "C34") (pin "2") (pinfunction "2_2") (pintype "passive"))
      (node (ref "L2") (pin "1") (pinfunction "1_1") (pintype "passive"))
    )
    (net (code "23") (name "Net-(C56-Pad1)") (class "Default")
      (node (ref "C56") (pin "1") (pinfunction "1_1") (pintype "passive"))
      (node (ref "R38") (pin "2") (pinfunction "2_2") (pintype "passive"))
    )
    (net (code "24") (name "Net-(C63-Pad1)") (class "Default")
      (node (ref "C63") (pin "1") (pinfunction "1_1") (pintype "passive"))
      (node (ref "FB8") (pin "2") (pinfunction "2_2") (pintype "passive"))
      (node (ref "R42") (pin "2") (pinfunction "2_2") (pintype "passive"))
    )
    (net (code "25") (name "Net-(PD5-0)") (class "Default")
      (node (ref "C34") (pin "1") (pinfunction "1_1") (pintype "passive"))
      (node (ref "D2") (pin "3") (pinfunction "3_3") (pintype "passive"))
      (node (ref "PD5") (pin "1") (pinfunction "0_1") (pintype "passive"))
    )
    (net (code "26") (name "Net-(PD7-0)") (class "Default")
      (node (ref "J1") (pin "3") (pinfunction "3_3") (pintype "passive"))
      (node (ref "PD7") (pin "1") (pinfunction "0_1") (pintype "passive"))
    )
    (net (code "27") (name "Net-(PD8-0)") (class "Default")
      (node (ref "J2") (pin "1") (pinfunction "1_1") (pintype "passive"))
      (node (ref "PD8") (pin "1") (pinfunction "0_1") (pintype "passive"))
    )
    (net (code "28") (name "Net-(U2-R12K)") (class "Default")
      (node (ref "R37") (pin "2") (pinfunction "2_2") (pintype "passive"))
      (node (ref "U2") (pin "48") (pinfunction "R12K_48") (pintype "passive"))
    )
    (net (code "29") (name "Net-(U2-REG_OUT)") (class "Default")
      (node (ref "L5") (pin "1") (pinfunction "1_1") (pintype "passive"))
      (node (ref "U2") (pin "24") (pinfunction "REG_OUT_24") (pintype "passive"))
    )
    (net (code "30") (name "Net-(U2-T_SCL)") (class "Default")
      (node (ref "R46") (pin "2") (pinfunction "2_2") (pintype "passive"))
      (node (ref "U2") (pin "16") (pinfunction "T_SCL_16") (pintype "passive"))
    )
    (net (code "31") (name "Net-(U2-T_SDA)") (class "Default")
      (node (ref "R47") (pin "2") (pinfunction "2_2") (pintype "passive"))
      (node (ref "U2") (pin "17") (pinfunction "T_SDA_17") (pintype "passive"))
    )
    (net (code "32") (name "Net-(U2-VCMI)") (class "Default")
      (node (ref "C45") (pin "2") (pinfunction "2_2") (pintype "passive"))
      (node (ref "U2") (pin "46") (pinfunction "VCMI_46") (pintype "passive"))
    )
    (net (code "33") (name "Net-(U2-VIN)") (class "Default")
      (node (ref "C51") (pin "1") (pinfunction "1_1") (pintype "passive"))
      (node (ref "U2") (pin "2") (pinfunction "VIN_2") (pintype "passive"))
    )
    (net (code "34") (name "Net-(U2-VIP)") (class "Default")
      (node (ref "C47") (pin "1") (pinfunction "1_1") (pintype "passive"))
      (node (ref "U2") (pin "1") (pinfunction "VIP_1") (pintype "passive"))
    )
    (net (code "35") (name "Net-(U2-XI)") (class "Default")
      (node (ref "C62") (pin "2") (pinfunction "2_2") (pintype "passive"))
      (node (ref "R41") (pin "1") (pinfunction "1_1") (pintype "passive"))
      (node (ref "U2") (pin "11") (pinfunction "XI_11") (pintype "passive"))
    )
    (net (code "36") (name "Net-(U2-XO)") (class "Default")
      (node (ref "R41") (pin "2") (pinfunction "2_2") (pintype "passive"))
      (node (ref "U2") (pin "10") (pinfunction "XO_10") (pintype "passive"))
    )
    (net (code "37") (name "Net-(U3-CP)") (class "Default")
      (node (ref "C53") (pin "2") (pinfunction "2_2") (pintype "passive"))
      (node (ref "R38") (pin "1") (pinfunction "1_1") (pintype "passive"))
      (node (ref "U3") (pin "15") (pinfunction "CP_15") (pintype "passive"))
    )
    (net (code "38") (name "Net-(U3-Det1)") (class "Default")
      (node (ref "C58") (pin "1") (pinfunction "1_1") (pintype "passive"))
      (node (ref "U3") (pin "4") (pinfunction "Det1_4") (pintype "passive"))
    )
    (net (code "39") (name "Net-(U3-Det2)") (class "Default")
      (node (ref "C59") (pin "1") (pinfunction "1_1") (pintype "passive"))
      (node (ref "U3") (pin "5") (pinfunction "Det2_5") (pintype "passive"))
    )
    (net (code "40") (name "Net-(U3-TF1N)") (class "Default")
      (node (ref "L4") (pin "1") (pinfunction "1_1") (pintype "passive"))
      (node (ref "U3") (pin "21") (pinfunction "TF1N_21") (pintype "passive"))
    )
    (net (code "41") (name "Net-(U3-TF1P)") (class "Default")
      (node (ref "L3") (pin "1") (pinfunction "1_1") (pintype "passive"))
      (node (ref "U3") (pin "22") (pinfunction "TF1P_22") (pintype "passive"))
    )
    (net (code "42") (name "Net-(U3-TF2N)") (class "Default")
      (node (ref "L4") (pin "2") (pinfunction "2_2") (pintype "passive"))
      (node (ref "U3") (pin "19") (pinfunction "TF2N_19") (pintype "passive"))
    )
    (net (code "43") (name "Net-(U3-TF2P)") (class "Default")
      (node (ref "L3") (pin "2") (pinfunction "2_2") (pintype "passive"))
      (node (ref "U3") (pin "20") (pinfunction "TF2P_20") (pintype "passive"))
    )
    (net (code "44") (name "Net-(U3-VDD_PLL)") (class "Default")
      (node (ref "C50") (pin "2") (pinfunction "2_2") (pintype "passive"))
      (node (ref "U3") (pin "17") (pinfunction "VDD_PLL_17") (pintype "passive"))
    )
    (net (code "45") (name "Net-(U3-Xtal_I)") (class "Default")
      (node (ref "J1") (pin "2") (pinfunction "2_2") (pintype "passive"))
      (node (ref "U3") (pin "8") (pinfunction "Xtal_I_8") (pintype "passive"))
    )
    (net (code "46") (name "Net-(U3-Xtal_O)") (class "Default")
      (node (ref "J2") (pin "2") (pinfunction "2_2") (pintype "passive"))
      (node (ref "U3") (pin "9") (pinfunction "Xtal_O_9") (pintype "passive"))
    )
    (net (code "47") (name "Net-(X1-GND{slash}NC)") (class "Default")
      (node (ref "J1") (pin "1") (pinfunction "1_1") (pintype "passive"))
      (node (ref "X1") (pin "1") (pinfunction "GND/NC_1") (pintype "passive"))
    )
    (net (code "48") (name "Net-(X1-OUT)") (class "Default")
      (node (ref "J2") (pin "3") (pinfunction "3_3") (pintype "passive"))
      (node (ref "X1") (pin "3") (pinfunction "OUT_3") (pintype "passive"))
    )
    (net (code "49") (name "VBUS") (class "Default")
      (node (ref "C35") (pin "2") (pinfunction "2_2") (pintype "passive"))
      (node (ref "U1") (pin "3") (pinfunction "IN_3") (pintype "power_in"))
    )
    (net (code "50") (name "unconnected-(IC3-WP-Pad7)") (class "Default")
      (node (ref "IC3") (pin "7") (pinfunction "WP_7") (pintype "passive+no_connect"))
    )
    (net (code "51") (name "unconnected-(U2-AGC_RF-Pad15)") (class "Default")
      (node (ref "U2") (pin "15") (pinfunction "AGC_RF_15") (pintype "passive+no_connect"))
    )
    (net (code "52") (name "unconnected-(U2-GPIO0-Pad37)") (class "Default")
      (node (ref "U2") (pin "37") (pinfunction "GPIO0_37") (pintype "passive+no_connect"))
    )
    (net (code "53") (name "unconnected-(U2-GPIO1-Pad32)") (class "Default")
      (node (ref "U2") (pin "32") (pinfunction "GPIO1_32") (pintype "passive+no_connect"))
    )
    (net (code "54") (name "unconnected-(U2-GPIO2-Pad31)") (class "Default")
      (node (ref "U2") (pin "31") (pinfunction "GPIO2_31") (pintype "passive+no_connect"))
    )
    (net (code "55") (name "unconnected-(U2-GPIO3-Pad36)") (class "Default")
      (node (ref "U2") (pin "36") (pinfunction "GPIO3_36") (pintype "passive+no_connect"))
    )
    (net (code "56") (name "unconnected-(U2-GPIO4-Pad30)") (class "Default")
      (node (ref "U2") (pin "30") (pinfunction "GPIO4_30") (pintype "passive+no_connect"))
    )
    (net (code "57") (name "unconnected-(U2-GPIO5-Pad29)") (class "Default")
      (node (ref "U2") (pin "29") (pinfunction "GPIO5_29") (pintype "passive+no_connect"))
    )
    (net (code "58") (name "unconnected-(U2-GPIO6-Pad22)") (class "Default")
      (node (ref "U2") (pin "22") (pinfunction "GPIO6_22") (pintype "passive+no_connect"))
    )
    (net (code "59") (name "unconnected-(U2-GPIO7-Pad21)") (class "Default")
      (node (ref "U2") (pin "21") (pinfunction "GPIO7_21") (pintype "passive+no_connect"))
    )
    (net (code "60") (name "unconnected-(U2-IR_RX_IN-Pad38)") (class "Default")
      (node (ref "U2") (pin "38") (pinfunction "IR_RX_IN_38") (pintype "passive+no_connect"))
    )
    (net (code "61") (name "unconnected-(U2-M_ERR-Pad35)") (class "Default")
      (node (ref "U2") (pin "35") (pinfunction "M_ERR_35") (pintype "passive+no_connect"))
    )
    (net (code "62") (name "unconnected-(U2-TP_CKO-Pad9)") (class "Default")
      (node (ref "U2") (pin "9") (pinfunction "TP_CKO_9") (pintype "passive+no_connect"))
    )
    (net (code "63") (name "unconnected-(U2-VINR-Pad6)") (class "Default")
      (node (ref "U2") (pin "6") (pinfunction "VINR_6") (pintype "passive+no_connect"))
    )
    (net (code "64") (name "unconnected-(U2-VQN-Pad5)") (class "Default")
      (node (ref "U2") (pin "5") (pinfunction "VQN_5") (pintype "passive+no_connect"))
    )
    (net (code "65") (name "unconnected-(U2-VQP-Pad4)") (class "Default")
      (node (ref "U2") (pin "4") (pinfunction "VQP_4") (pintype "passive+no_connect"))
    )
    (net (code "66") (name "unconnected-(U3-Loop-Pad3)") (class "Default")
      (node (ref "U3") (pin "3") (pinfunction "Loop_3") (pintype "passive+no_connect"))
    )
    (net (code "67") (name "unconnected-(U3-NC-Pad1)") (class "Default")
      (node (ref "U3") (pin "1") (pinfunction "NC_1") (pintype "passive+no_connect"))
    )
  )
)
